# Sheet1.net
KiCad netlist of a schematic drawn in Altium Designer
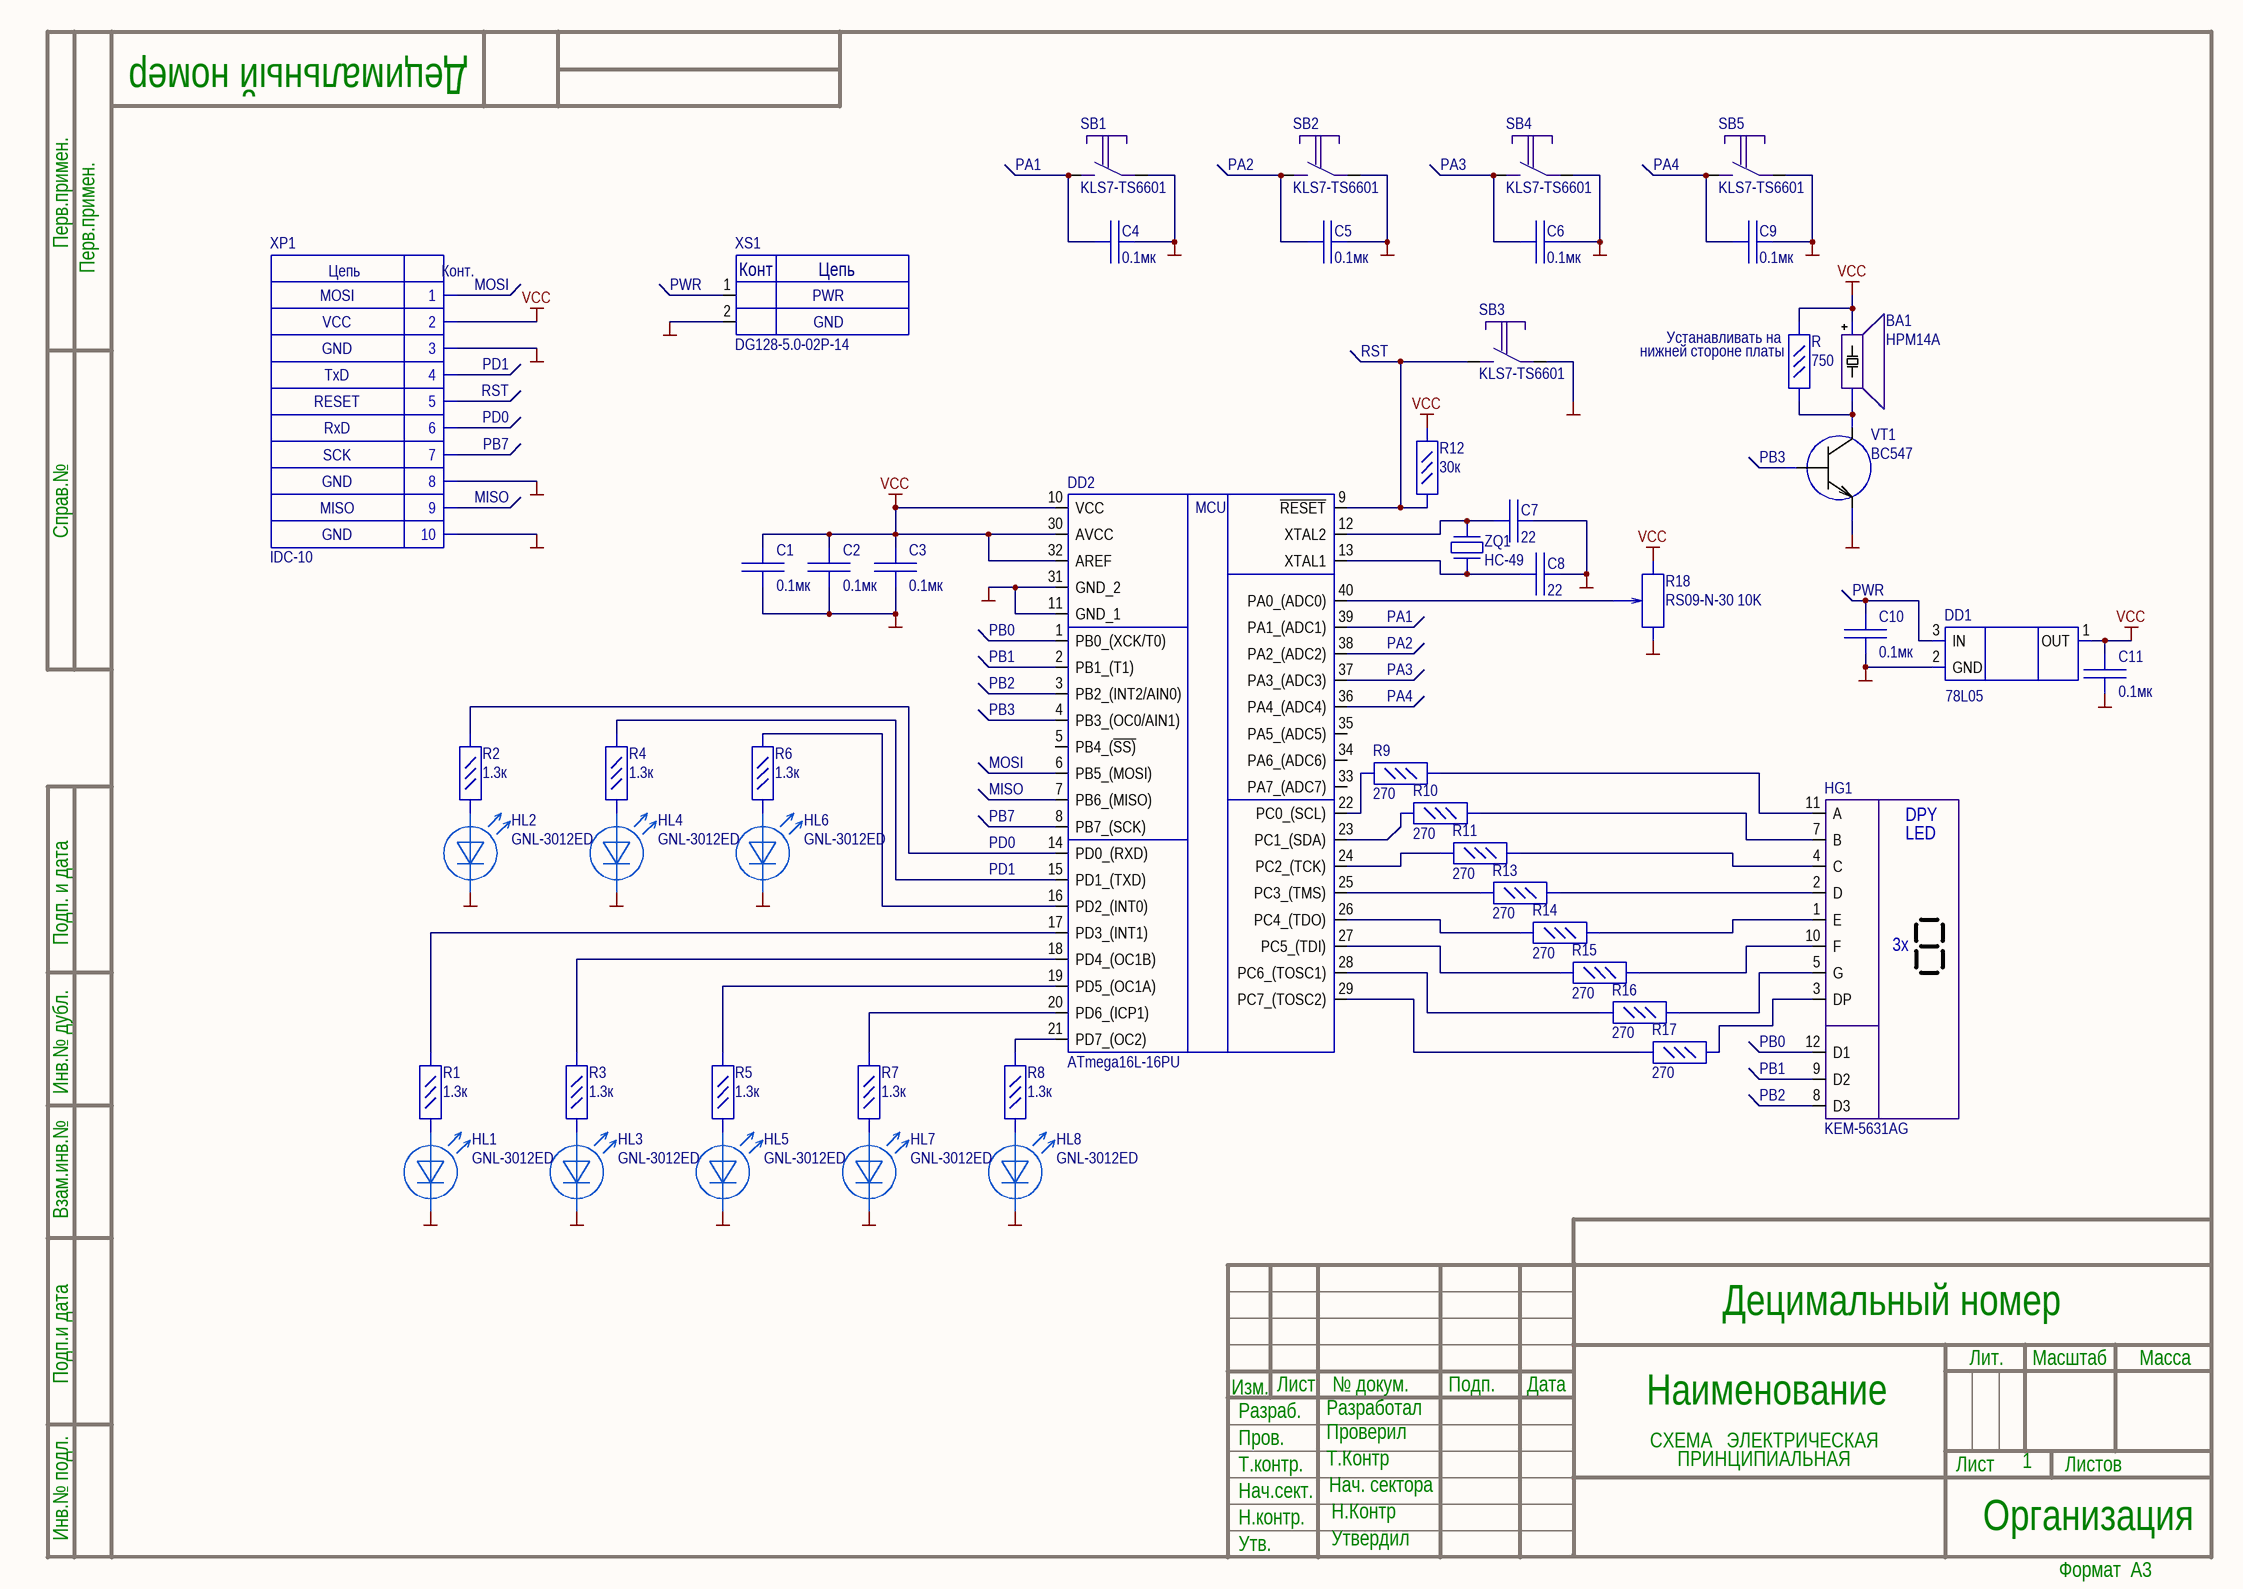
[diagram p0: Sheet1.SchDoc]

(export (version "E")
  (design (tool "Eeschema 10.0.6"))
  (components
    (comp (ref "BA1") (value "HPM14A") (footprint "HPM14A") (libsource (lib "11.Other") (part "HPM14A")))
    (comp (ref "C1")
      (value "0.1мк")
      (footprint "К10-17Б")
      (libsource (lib "2.Capasitors") (part "C_К10-17Б"))
    )
    (comp (ref "C2")
      (value "0.1мк")
      (footprint "К10-17Б")
      (libsource (lib "2.Capasitors") (part "C_К10-17Б"))
    )
    (comp (ref "C3")
      (value "0.1мк")
      (footprint "К10-17Б")
      (libsource (lib "2.Capasitors") (part "C_К10-17Б"))
    )
    (comp (ref "C4")
      (value "0.1мк")
      (footprint "К10-17Б")
      (libsource (lib "2.Capasitors") (part "C_К10-17Б"))
    )
    (comp (ref "C5")
      (value "0.1мк")
      (footprint "К10-17Б")
      (libsource (lib "2.Capasitors") (part "C_К10-17Б"))
    )
    (comp (ref "C6")
      (value "0.1мк")
      (footprint "К10-17Б")
      (libsource (lib "2.Capasitors") (part "C_К10-17Б"))
    )
    (comp (ref "C7") (value "22") (footprint "К10-17Б") (libsource (lib "2.Capasitors") (part "C_К10-17Б")))
    (comp (ref "C8") (value "22") (footprint "К10-17Б") (libsource (lib "2.Capasitors") (part "C_К10-17Б")))
    (comp (ref "C9")
      (value "0.1мк")
      (footprint "К10-17Б")
      (libsource (lib "2.Capasitors") (part "C_К10-17Б"))
    )
    (comp (ref "C10")
      (value "0.1мк")
      (footprint "К10-17Б")
      (libsource (lib "2.Capasitors") (part "C_К10-17Б"))
    )
    (comp (ref "C11")
      (value "0.1мк")
      (footprint "К10-17Б")
      (libsource (lib "2.Capasitors") (part "C_К10-17Б"))
    )
    (comp (ref "DD1")
      (value "78L05")
      (footprint "КТ-26")
      (description "LDO преобразователь")
      (libsource (lib "10.Power_converters") (part "78L05"))
    )
    (comp (ref "DD2")
      (value "ATmega16L-16PU")
      (footprint "PcbLib:DIP-40")
      (description "ATmega16-16PU, Микроконтроллер 8-Бит, AVR, 16МГц, 16КБ Flash [DIP-40]")
      (fields
        (field (name "MANUFACTURER_PART_NUMBER") "ATmega16L-8PU")
        (field (name "MOUSER PART NUMBER") "556-ATMEGA16L-8PU")
      )
      (libsource (lib "6.Chips") (part "ATmega16L-8PU"))
    )
    (comp (ref "HG1")
      (value "KEM-5631AG")
      (footprint "BC56")
      (description "Индикатор красный ОК, 14.2мм 3х7, 10.5мКд")
      (libsource (lib "11.Other") (part "BC56-12SRWA"))
    )
    (comp (ref "HL1")
      (value "GNL-3012ED")
      (footprint "GNL-3012ED")
      (libsource (lib "4.Diodes") (part "GNL-3012ED"))
    )
    (comp (ref "HL2")
      (value "GNL-3012ED")
      (footprint "GNL-3012ED")
      (libsource (lib "4.Diodes") (part "GNL-3012ED"))
    )
    (comp (ref "HL3")
      (value "GNL-3012ED")
      (footprint "GNL-3012ED")
      (libsource (lib "4.Diodes") (part "GNL-3012ED"))
    )
    (comp (ref "HL4")
      (value "GNL-3012ED")
      (footprint "GNL-3012ED")
      (libsource (lib "4.Diodes") (part "GNL-3012ED"))
    )
    (comp (ref "HL5")
      (value "GNL-3012ED")
      (footprint "GNL-3012ED")
      (libsource (lib "4.Diodes") (part "GNL-3012ED"))
    )
    (comp (ref "HL6")
      (value "GNL-3012ED")
      (footprint "GNL-3012ED")
      (libsource (lib "4.Diodes") (part "GNL-3012ED"))
    )
    (comp (ref "HL7")
      (value "GNL-3012ED")
      (footprint "GNL-3012ED")
      (libsource (lib "4.Diodes") (part "GNL-3012ED"))
    )
    (comp (ref "HL8")
      (value "GNL-3012ED")
      (footprint "GNL-3012ED")
      (libsource (lib "4.Diodes") (part "GNL-3012ED"))
    )
    (comp (ref "R") (value "750") (footprint "С2-23_2W_R") (libsource (lib "1.Resistors") (part "R_DIP")))
    (comp (ref "R1") (value "1.3к") (footprint "С2-23_2W_R") (libsource (lib "1.Resistors") (part "R_DIP")))
    (comp (ref "R2") (value "1.3к") (footprint "С2-23_2W_R") (libsource (lib "1.Resistors") (part "R_DIP")))
    (comp (ref "R3") (value "1.3к") (footprint "С2-23_2W_R") (libsource (lib "1.Resistors") (part "R_DIP")))
    (comp (ref "R4") (value "1.3к") (footprint "С2-23_2W_R") (libsource (lib "1.Resistors") (part "R_DIP")))
    (comp (ref "R5") (value "1.3к") (footprint "С2-23_2W_R") (libsource (lib "1.Resistors") (part "R_DIP")))
    (comp (ref "R6") (value "1.3к") (footprint "С2-23_2W_R") (libsource (lib "1.Resistors") (part "R_DIP")))
    (comp (ref "R7") (value "1.3к") (footprint "С2-23_2W_R") (libsource (lib "1.Resistors") (part "R_DIP")))
    (comp (ref "R8") (value "1.3к") (footprint "С2-23_2W_R") (libsource (lib "1.Resistors") (part "R_DIP")))
    (comp (ref "R9") (value "270") (footprint "С2-23_2W_R") (libsource (lib "1.Resistors") (part "R_DIP")))
    (comp (ref "R10") (value "270") (footprint "С2-23_2W_R") (libsource (lib "1.Resistors") (part "R_DIP")))
    (comp (ref "R11") (value "270") (footprint "С2-23_2W_R") (libsource (lib "1.Resistors") (part "R_DIP")))
    (comp (ref "R12") (value "30к") (footprint "С2-23_2W_R") (libsource (lib "1.Resistors") (part "R_DIP")))
    (comp (ref "R13") (value "270") (footprint "С2-23_2W_R") (libsource (lib "1.Resistors") (part "R_DIP")))
    (comp (ref "R14") (value "270") (footprint "С2-23_2W_R") (libsource (lib "1.Resistors") (part "R_DIP")))
    (comp (ref "R15") (value "270") (footprint "С2-23_2W_R") (libsource (lib "1.Resistors") (part "R_DIP")))
    (comp (ref "R16") (value "270") (footprint "С2-23_2W_R") (libsource (lib "1.Resistors") (part "R_DIP")))
    (comp (ref "R17") (value "270") (footprint "С2-23_2W_R") (libsource (lib "1.Resistors") (part "R_DIP")))
    (comp (ref "R18")
      (value "RS09-N-30 10K")
      (footprint "PTV09A-1")
      (description "10 кОм, Резистор переменный")
      (libsource (lib "12.Trimmers") (part "PTV09A-4225F-B103"))
    )
    (comp (ref "SB1")
      (value "KLS7-TS6601")
      (footprint "KLS7-TS6601")
      (libsource (lib "9.Commutation") (part "KLS7-TS6601"))
    )
    (comp (ref "SB2")
      (value "KLS7-TS6601")
      (footprint "KLS7-TS6601")
      (libsource (lib "9.Commutation") (part "KLS7-TS6601"))
    )
    (comp (ref "SB3")
      (value "KLS7-TS6601")
      (footprint "KLS7-TS6601")
      (libsource (lib "9.Commutation") (part "KLS7-TS6601"))
    )
    (comp (ref "SB4")
      (value "KLS7-TS6601")
      (footprint "KLS7-TS6601")
      (libsource (lib "9.Commutation") (part "KLS7-TS6601"))
    )
    (comp (ref "SB5")
      (value "KLS7-TS6601")
      (footprint "KLS7-TS6601")
      (libsource (lib "9.Commutation") (part "KLS7-TS6601"))
    )
    (comp (ref "VT1") (value "BC547") (footprint "КТ-26") (libsource (lib "5.Transistors") (part "BC547")))
    (comp (ref "XP1") (value "IDC-10") (footprint "IDC-10") (libsource (lib "7.Connectors") (part "IDC-10")))
    (comp (ref "XS1")
      (value "DG128-5.0-02P-14")
      (footprint "DG128-5.0-02P-14")
      (libsource (lib "7.Connectors") (part "DG128-5.0-02P-14"))
    )
    (comp (ref "ZQ1") (value "HC-49") (footprint "HC-49") (libsource (lib "8.Resonarors") (part "HC-49")))
  )
  (nets
    (net (code "1") (name "/MISO") (class "Default")
      (node (ref "DD2") (pin "7") (pinfunction "PB6_(MISO)_7") (pintype "passive"))
      (node (ref "XP1") (pin "9") (pinfunction "9_9") (pintype "passive"))
    )
    (net (code "2") (name "/MOSI") (class "Default")
      (node (ref "DD2") (pin "6") (pinfunction "PB5_(MOSI)_6") (pintype "passive"))
      (node (ref "XP1") (pin "1") (pinfunction "1_1") (pintype "passive"))
    )
    (net (code "3") (name "/PA1") (class "Default")
      (node (ref "C4") (pin "2") (pinfunction "2_2") (pintype "passive"))
      (node (ref "DD2") (pin "39") (pinfunction "PA1_(ADC1)_39") (pintype "passive"))
      (node (ref "SB1") (pin "1") (pinfunction "1_1") (pintype "passive"))
    )
    (net (code "4") (name "/PA2") (class "Default")
      (node (ref "C5") (pin "2") (pinfunction "2_2") (pintype "passive"))
      (node (ref "DD2") (pin "38") (pinfunction "PA2_(ADC2)_38") (pintype "passive"))
      (node (ref "SB2") (pin "1") (pinfunction "1_1") (pintype "passive"))
    )
    (net (code "5") (name "/PA3") (class "Default")
      (node (ref "C6") (pin "2") (pinfunction "2_2") (pintype "passive"))
      (node (ref "DD2") (pin "37") (pinfunction "PA3_(ADC3)_37") (pintype "passive"))
      (node (ref "SB4") (pin "1") (pinfunction "1_1") (pintype "passive"))
    )
    (net (code "6") (name "/PA4") (class "Default")
      (node (ref "C9") (pin "2") (pinfunction "2_2") (pintype "passive"))
      (node (ref "DD2") (pin "36") (pinfunction "PA4_(ADC4)_36") (pintype "passive"))
      (node (ref "SB5") (pin "1") (pinfunction "1_1") (pintype "passive"))
    )
    (net (code "7") (name "/PB0") (class "Default")
      (node (ref "DD2") (pin "1") (pinfunction "PB0_(XCK/T0)_1") (pintype "passive"))
      (node (ref "HG1") (pin "12") (pinfunction "D1_12") (pintype "passive"))
    )
    (net (code "8") (name "/PB1") (class "Default")
      (node (ref "DD2") (pin "2") (pinfunction "PB1_(T1)_2") (pintype "passive"))
      (node (ref "HG1") (pin "9") (pinfunction "D2_9") (pintype "passive"))
    )
    (net (code "9") (name "/PB2") (class "Default")
      (node (ref "DD2") (pin "3") (pinfunction "PB2_(INT2/AIN0)_3") (pintype "passive"))
      (node (ref "HG1") (pin "8") (pinfunction "D3_8") (pintype "passive"))
    )
    (net (code "10") (name "/PB3") (class "Default")
      (node (ref "DD2") (pin "4") (pinfunction "PB3_(OC0/AIN1)_4") (pintype "passive"))
      (node (ref "VT1") (pin "2") (pinfunction "B_2") (pintype "passive"))
    )
    (net (code "11") (name "/PB7") (class "Default")
      (node (ref "DD2") (pin "8") (pinfunction "PB7_(SCK)_8") (pintype "passive"))
      (node (ref "XP1") (pin "7") (pinfunction "7_7") (pintype "passive"))
    )
    (net (code "12") (name "/PD0") (class "Default")
      (node (ref "DD2") (pin "14") (pinfunction "PD0_(RXD)_14") (pintype "passive"))
      (node (ref "R2") (pin "2") (pinfunction "2_2") (pintype "passive"))
      (node (ref "XP1") (pin "6") (pinfunction "6_6") (pintype "passive"))
    )
    (net (code "13") (name "/PD1") (class "Default")
      (node (ref "DD2") (pin "15") (pinfunction "PD1_(TXD)_15") (pintype "passive"))
      (node (ref "R4") (pin "2") (pinfunction "2_2") (pintype "passive"))
      (node (ref "XP1") (pin "4") (pinfunction "4_4") (pintype "passive"))
    )
    (net (code "14") (name "/PWR") (class "Default")
      (node (ref "C10") (pin "2") (pinfunction "2_2") (pintype "passive"))
      (node (ref "DD1") (pin "3") (pinfunction "IN_3") (pintype "passive"))
      (node (ref "XS1") (pin "1") (pintype "passive"))
    )
    (net (code "15") (name "/RST") (class "Default")
      (node (ref "DD2") (pin "9") (pinfunction "~{RESET}_9") (pintype "passive"))
      (node (ref "R12") (pin "2") (pinfunction "2_2") (pintype "passive"))
      (node (ref "SB3") (pin "1") (pinfunction "1_1") (pintype "passive"))
      (node (ref "XP1") (pin "5") (pinfunction "5_5") (pintype "passive"))
    )
    (net (code "16") (name "GND") (class "Default")
      (node (ref "C1") (pin "1") (pinfunction "1_1") (pintype "passive"))
      (node (ref "C10") (pin "1") (pinfunction "1_1") (pintype "passive"))
      (node (ref "C11") (pin "1") (pinfunction "1_1") (pintype "passive"))
      (node (ref "C2") (pin "1") (pinfunction "1_1") (pintype "passive"))
      (node (ref "C3") (pin "1") (pinfunction "1_1") (pintype "passive"))
      (node (ref "C4") (pin "1") (pinfunction "1_1") (pintype "passive"))
      (node (ref "C5") (pin "1") (pinfunction "1_1") (pintype "passive"))
      (node (ref "C6") (pin "1") (pinfunction "1_1") (pintype "passive"))
      (node (ref "C7") (pin "2") (pinfunction "2_2") (pintype "passive"))
      (node (ref "C8") (pin "2") (pinfunction "2_2") (pintype "passive"))
      (node (ref "C9") (pin "1") (pinfunction "1_1") (pintype "passive"))
      (node (ref "DD1") (pin "2") (pinfunction "GND_2") (pintype "passive"))
      (node (ref "DD2") (pin "11") (pinfunction "GND_1_11") (pintype "passive"))
      (node (ref "DD2") (pin "31") (pinfunction "GND_2_31") (pintype "passive"))
      (node (ref "HL1") (pin "2") (pinfunction "2_2") (pintype "passive"))
      (node (ref "HL2") (pin "2") (pinfunction "2_2") (pintype "passive"))
      (node (ref "HL3") (pin "2") (pinfunction "2_2") (pintype "passive"))
      (node (ref "HL4") (pin "2") (pinfunction "2_2") (pintype "passive"))
      (node (ref "HL5") (pin "2") (pinfunction "2_2") (pintype "passive"))
      (node (ref "HL6") (pin "2") (pinfunction "2_2") (pintype "passive"))
      (node (ref "HL7") (pin "2") (pinfunction "2_2") (pintype "passive"))
      (node (ref "HL8") (pin "2") (pinfunction "2_2") (pintype "passive"))
      (node (ref "R18") (pin "1") (pinfunction "1_1") (pintype "passive"))
      (node (ref "SB1") (pin "2") (pinfunction "2_2") (pintype "passive"))
      (node (ref "SB2") (pin "2") (pinfunction "2_2") (pintype "passive"))
      (node (ref "SB3") (pin "2") (pinfunction "2_2") (pintype "passive"))
      (node (ref "SB4") (pin "2") (pinfunction "2_2") (pintype "passive"))
      (node (ref "SB5") (pin "2") (pinfunction "2_2") (pintype "passive"))
      (node (ref "VT1") (pin "3") (pinfunction "E_3") (pintype "passive"))
      (node (ref "XP1") (pin "10") (pinfunction "10_10") (pintype "passive"))
      (node (ref "XP1") (pin "3") (pinfunction "3_3") (pintype "passive"))
      (node (ref "XP1") (pin "8") (pinfunction "8_8") (pintype "passive"))
      (node (ref "XS1") (pin "2") (pintype "passive"))
    )
    (net (code "17") (name "Net-(DD2-PA0_(ADC0))") (class "Default")
      (node (ref "DD2") (pin "40") (pinfunction "PA0_(ADC0)_40") (pintype "passive"))
      (node (ref "R18") (pin "2") (pinfunction "2_2") (pintype "passive"))
    )
    (net (code "18") (name "Net-(DD2-PC0_(SCL))") (class "Default")
      (node (ref "DD2") (pin "22") (pinfunction "PC0_(SCL)_22") (pintype "passive"))
      (node (ref "R9") (pin "1") (pinfunction "1_1") (pintype "passive"))
    )
    (net (code "19") (name "Net-(DD2-PC1_(SDA))") (class "Default")
      (node (ref "DD2") (pin "23") (pinfunction "PC1_(SDA)_23") (pintype "passive"))
      (node (ref "R10") (pin "1") (pinfunction "1_1") (pintype "passive"))
    )
    (net (code "20") (name "Net-(DD2-PC2_(TCK))") (class "Default")
      (node (ref "DD2") (pin "24") (pinfunction "PC2_(TCK)_24") (pintype "passive"))
      (node (ref "R11") (pin "1") (pinfunction "1_1") (pintype "passive"))
    )
    (net (code "21") (name "Net-(DD2-PC3_(TMS))") (class "Default")
      (node (ref "DD2") (pin "25") (pinfunction "PC3_(TMS)_25") (pintype "passive"))
      (node (ref "R13") (pin "1") (pinfunction "1_1") (pintype "passive"))
    )
    (net (code "22") (name "Net-(DD2-PC4_(TDO))") (class "Default")
      (node (ref "DD2") (pin "26") (pinfunction "PC4_(TDO)_26") (pintype "passive"))
      (node (ref "R14") (pin "1") (pinfunction "1_1") (pintype "passive"))
    )
    (net (code "23") (name "Net-(DD2-PC5_(TDI))") (class "Default")
      (node (ref "DD2") (pin "27") (pinfunction "PC5_(TDI)_27") (pintype "passive"))
      (node (ref "R15") (pin "1") (pinfunction "1_1") (pintype "passive"))
    )
    (net (code "24") (name "Net-(DD2-PC6_(TOSC1))") (class "Default")
      (node (ref "DD2") (pin "28") (pinfunction "PC6_(TOSC1)_28") (pintype "passive"))
      (node (ref "R16") (pin "1") (pinfunction "1_1") (pintype "passive"))
    )
    (net (code "25") (name "Net-(DD2-PC7_(TOSC2))") (class "Default")
      (node (ref "DD2") (pin "29") (pinfunction "PC7_(TOSC2)_29") (pintype "passive"))
      (node (ref "R17") (pin "1") (pinfunction "1_1") (pintype "passive"))
    )
    (net (code "26") (name "Net-(DD2-PD2_(INT0))") (class "Default")
      (node (ref "DD2") (pin "16") (pinfunction "PD2_(INT0)_16") (pintype "passive"))
      (node (ref "R6") (pin "2") (pinfunction "2_2") (pintype "passive"))
    )
    (net (code "27") (name "Net-(DD2-PD3_(INT1))") (class "Default")
      (node (ref "DD2") (pin "17") (pinfunction "PD3_(INT1)_17") (pintype "passive"))
      (node (ref "R1") (pin "2") (pinfunction "2_2") (pintype "passive"))
    )
    (net (code "28") (name "Net-(DD2-PD4_(OC1B))") (class "Default")
      (node (ref "DD2") (pin "18") (pinfunction "PD4_(OC1B)_18") (pintype "passive"))
      (node (ref "R3") (pin "2") (pinfunction "2_2") (pintype "passive"))
    )
    (net (code "29") (name "Net-(DD2-PD5_(OC1A))") (class "Default")
      (node (ref "DD2") (pin "19") (pinfunction "PD5_(OC1A)_19") (pintype "passive"))
      (node (ref "R5") (pin "2") (pinfunction "2_2") (pintype "passive"))
    )
    (net (code "30") (name "Net-(DD2-PD6_(ICP1))") (class "Default")
      (node (ref "DD2") (pin "20") (pinfunction "PD6_(ICP1)_20") (pintype "passive"))
      (node (ref "R7") (pin "2") (pinfunction "2_2") (pintype "passive"))
    )
    (net (code "31") (name "Net-(DD2-PD7_(OC2))") (class "Default")
      (node (ref "DD2") (pin "21") (pinfunction "PD7_(OC2)_21") (pintype "passive"))
      (node (ref "R8") (pin "2") (pinfunction "2_2") (pintype "passive"))
    )
    (net (code "32") (name "Net-(DD2-XTAL1)") (class "Default")
      (node (ref "C8") (pin "1") (pinfunction "1_1") (pintype "passive"))
      (node (ref "DD2") (pin "13") (pinfunction "XTAL1_13") (pintype "passive"))
      (node (ref "ZQ1") (pin "2") (pinfunction "2_2") (pintype "passive"))
    )
    (net (code "33") (name "Net-(DD2-XTAL2)") (class "Default")
      (node (ref "C7") (pin "1") (pinfunction "1_1") (pintype "passive"))
      (node (ref "DD2") (pin "12") (pinfunction "XTAL2_12") (pintype "passive"))
      (node (ref "ZQ1") (pin "1") (pinfunction "1_1") (pintype "passive"))
    )
    (net (code "34") (name "Net-(HG1-A)") (class "Default")
      (node (ref "HG1") (pin "11") (pinfunction "A_11") (pintype "passive"))
      (node (ref "R9") (pin "2") (pinfunction "2_2") (pintype "passive"))
    )
    (net (code "35") (name "Net-(HG1-B)") (class "Default")
      (node (ref "HG1") (pin "7") (pinfunction "B_7") (pintype "passive"))
      (node (ref "R10") (pin "2") (pinfunction "2_2") (pintype "passive"))
    )
    (net (code "36") (name "Net-(HG1-C)") (class "Default")
      (node (ref "HG1") (pin "4") (pinfunction "C_4") (pintype "passive"))
      (node (ref "R11") (pin "2") (pinfunction "2_2") (pintype "passive"))
    )
    (net (code "37") (name "Net-(HG1-D)") (class "Default")
      (node (ref "HG1") (pin "2") (pinfunction "D_2") (pintype "passive"))
      (node (ref "R13") (pin "2") (pinfunction "2_2") (pintype "passive"))
    )
    (net (code "38") (name "Net-(HG1-DP)") (class "Default")
      (node (ref "HG1") (pin "3") (pinfunction "DP_3") (pintype "passive"))
      (node (ref "R17") (pin "2") (pinfunction "2_2") (pintype "passive"))
    )
    (net (code "39") (name "Net-(HG1-E)") (class "Default")
      (node (ref "HG1") (pin "1") (pinfunction "E_1") (pintype "passive"))
      (node (ref "R14") (pin "2") (pinfunction "2_2") (pintype "passive"))
    )
    (net (code "40") (name "Net-(HG1-F)") (class "Default")
      (node (ref "HG1") (pin "10") (pinfunction "F_10") (pintype "passive"))
      (node (ref "R15") (pin "2") (pinfunction "2_2") (pintype "passive"))
    )
    (net (code "41") (name "Net-(HG1-G)") (class "Default")
      (node (ref "HG1") (pin "5") (pinfunction "G_5") (pintype "passive"))
      (node (ref "R16") (pin "2") (pinfunction "2_2") (pintype "passive"))
    )
    (net (code "42") (name "Net-(HL1-Pad1)") (class "Default")
      (node (ref "HL1") (pin "1") (pinfunction "1_1") (pintype "passive"))
      (node (ref "R1") (pin "1") (pinfunction "1_1") (pintype "passive"))
    )
    (net (code "43") (name "Net-(HL2-Pad1)") (class "Default")
      (node (ref "HL2") (pin "1") (pinfunction "1_1") (pintype "passive"))
      (node (ref "R2") (pin "1") (pinfunction "1_1") (pintype "passive"))
    )
    (net (code "44") (name "Net-(HL3-Pad1)") (class "Default")
      (node (ref "HL3") (pin "1") (pinfunction "1_1") (pintype "passive"))
      (node (ref "R3") (pin "1") (pinfunction "1_1") (pintype "passive"))
    )
    (net (code "45") (name "Net-(HL4-Pad1)") (class "Default")
      (node (ref "HL4") (pin "1") (pinfunction "1_1") (pintype "passive"))
      (node (ref "R4") (pin "1") (pinfunction "1_1") (pintype "passive"))
    )
    (net (code "46") (name "Net-(HL5-Pad1)") (class "Default")
      (node (ref "HL5") (pin "1") (pinfunction "1_1") (pintype "passive"))
      (node (ref "R5") (pin "1") (pinfunction "1_1") (pintype "passive"))
    )
    (net (code "47") (name "Net-(HL6-Pad1)") (class "Default")
      (node (ref "HL6") (pin "1") (pinfunction "1_1") (pintype "passive"))
      (node (ref "R6") (pin "1") (pinfunction "1_1") (pintype "passive"))
    )
    (net (code "48") (name "Net-(HL7-Pad1)") (class "Default")
      (node (ref "HL7") (pin "1") (pinfunction "1_1") (pintype "passive"))
      (node (ref "R7") (pin "1") (pinfunction "1_1") (pintype "passive"))
    )
    (net (code "49") (name "Net-(HL8-Pad1)") (class "Default")
      (node (ref "HL8") (pin "1") (pinfunction "1_1") (pintype "passive"))
      (node (ref "R8") (pin "1") (pinfunction "1_1") (pintype "passive"))
    )
    (net (code "50") (name "Net-(VT1-C)") (class "Default")
      (node (ref "BA1") (pin "2") (pinfunction "2_2") (pintype "passive"))
      (node (ref "R") (pin "1") (pinfunction "1_1") (pintype "passive"))
      (node (ref "VT1") (pin "1") (pinfunction "C_1") (pintype "passive"))
    )
    (net (code "51") (name "VCC") (class "Default")
      (node (ref "BA1") (pin "1") (pinfunction "1_1") (pintype "passive"))
      (node (ref "C1") (pin "2") (pinfunction "2_2") (pintype "passive"))
      (node (ref "C11") (pin "2") (pinfunction "2_2") (pintype "passive"))
      (node (ref "C2") (pin "2") (pinfunction "2_2") (pintype "passive"))
      (node (ref "C3") (pin "2") (pinfunction "2_2") (pintype "passive"))
      (node (ref "DD1") (pin "1") (pinfunction "OUT_1") (pintype "passive"))
      (node (ref "DD2") (pin "10") (pinfunction "VCC_10") (pintype "passive"))
      (node (ref "DD2") (pin "30") (pinfunction "AVCC_30") (pintype "passive"))
      (node (ref "DD2") (pin "32") (pinfunction "AREF_32") (pintype "passive"))
      (node (ref "R") (pin "2") (pinfunction "2_2") (pintype "passive"))
      (node (ref "R12") (pin "1") (pinfunction "1_1") (pintype "passive"))
      (node (ref "R18") (pin "3") (pinfunction "3_3") (pintype "passive"))
      (node (ref "XP1") (pin "2") (pinfunction "2_2") (pintype "passive"))
    )
    (net (code "52") (name "unconnected-(DD2-PA5_(ADC5)-Pad35)") (class "Default")
      (node (ref "DD2") (pin "35") (pinfunction "PA5_(ADC5)_35") (pintype "passive"))
    )
    (net (code "53") (name "unconnected-(DD2-PA6_(ADC6)-Pad34)") (class "Default")
      (node (ref "DD2") (pin "34") (pinfunction "PA6_(ADC6)_34") (pintype "passive"))
    )
    (net (code "54") (name "unconnected-(DD2-PA7_(ADC7)-Pad33)") (class "Default")
      (node (ref "DD2") (pin "33") (pinfunction "PA7_(ADC7)_33") (pintype "passive"))
    )
    (net (code "55") (name "unconnected-(DD2-PB4_(~{SS)}-Pad5)") (class "Default")
      (node (ref "DD2") (pin "5") (pinfunction "PB4_(~{SS)}_5") (pintype "passive"))
    )
  )
)
